# ZIntermediar2024.net
KiCad netlist of a schematic drawn in EAGLE
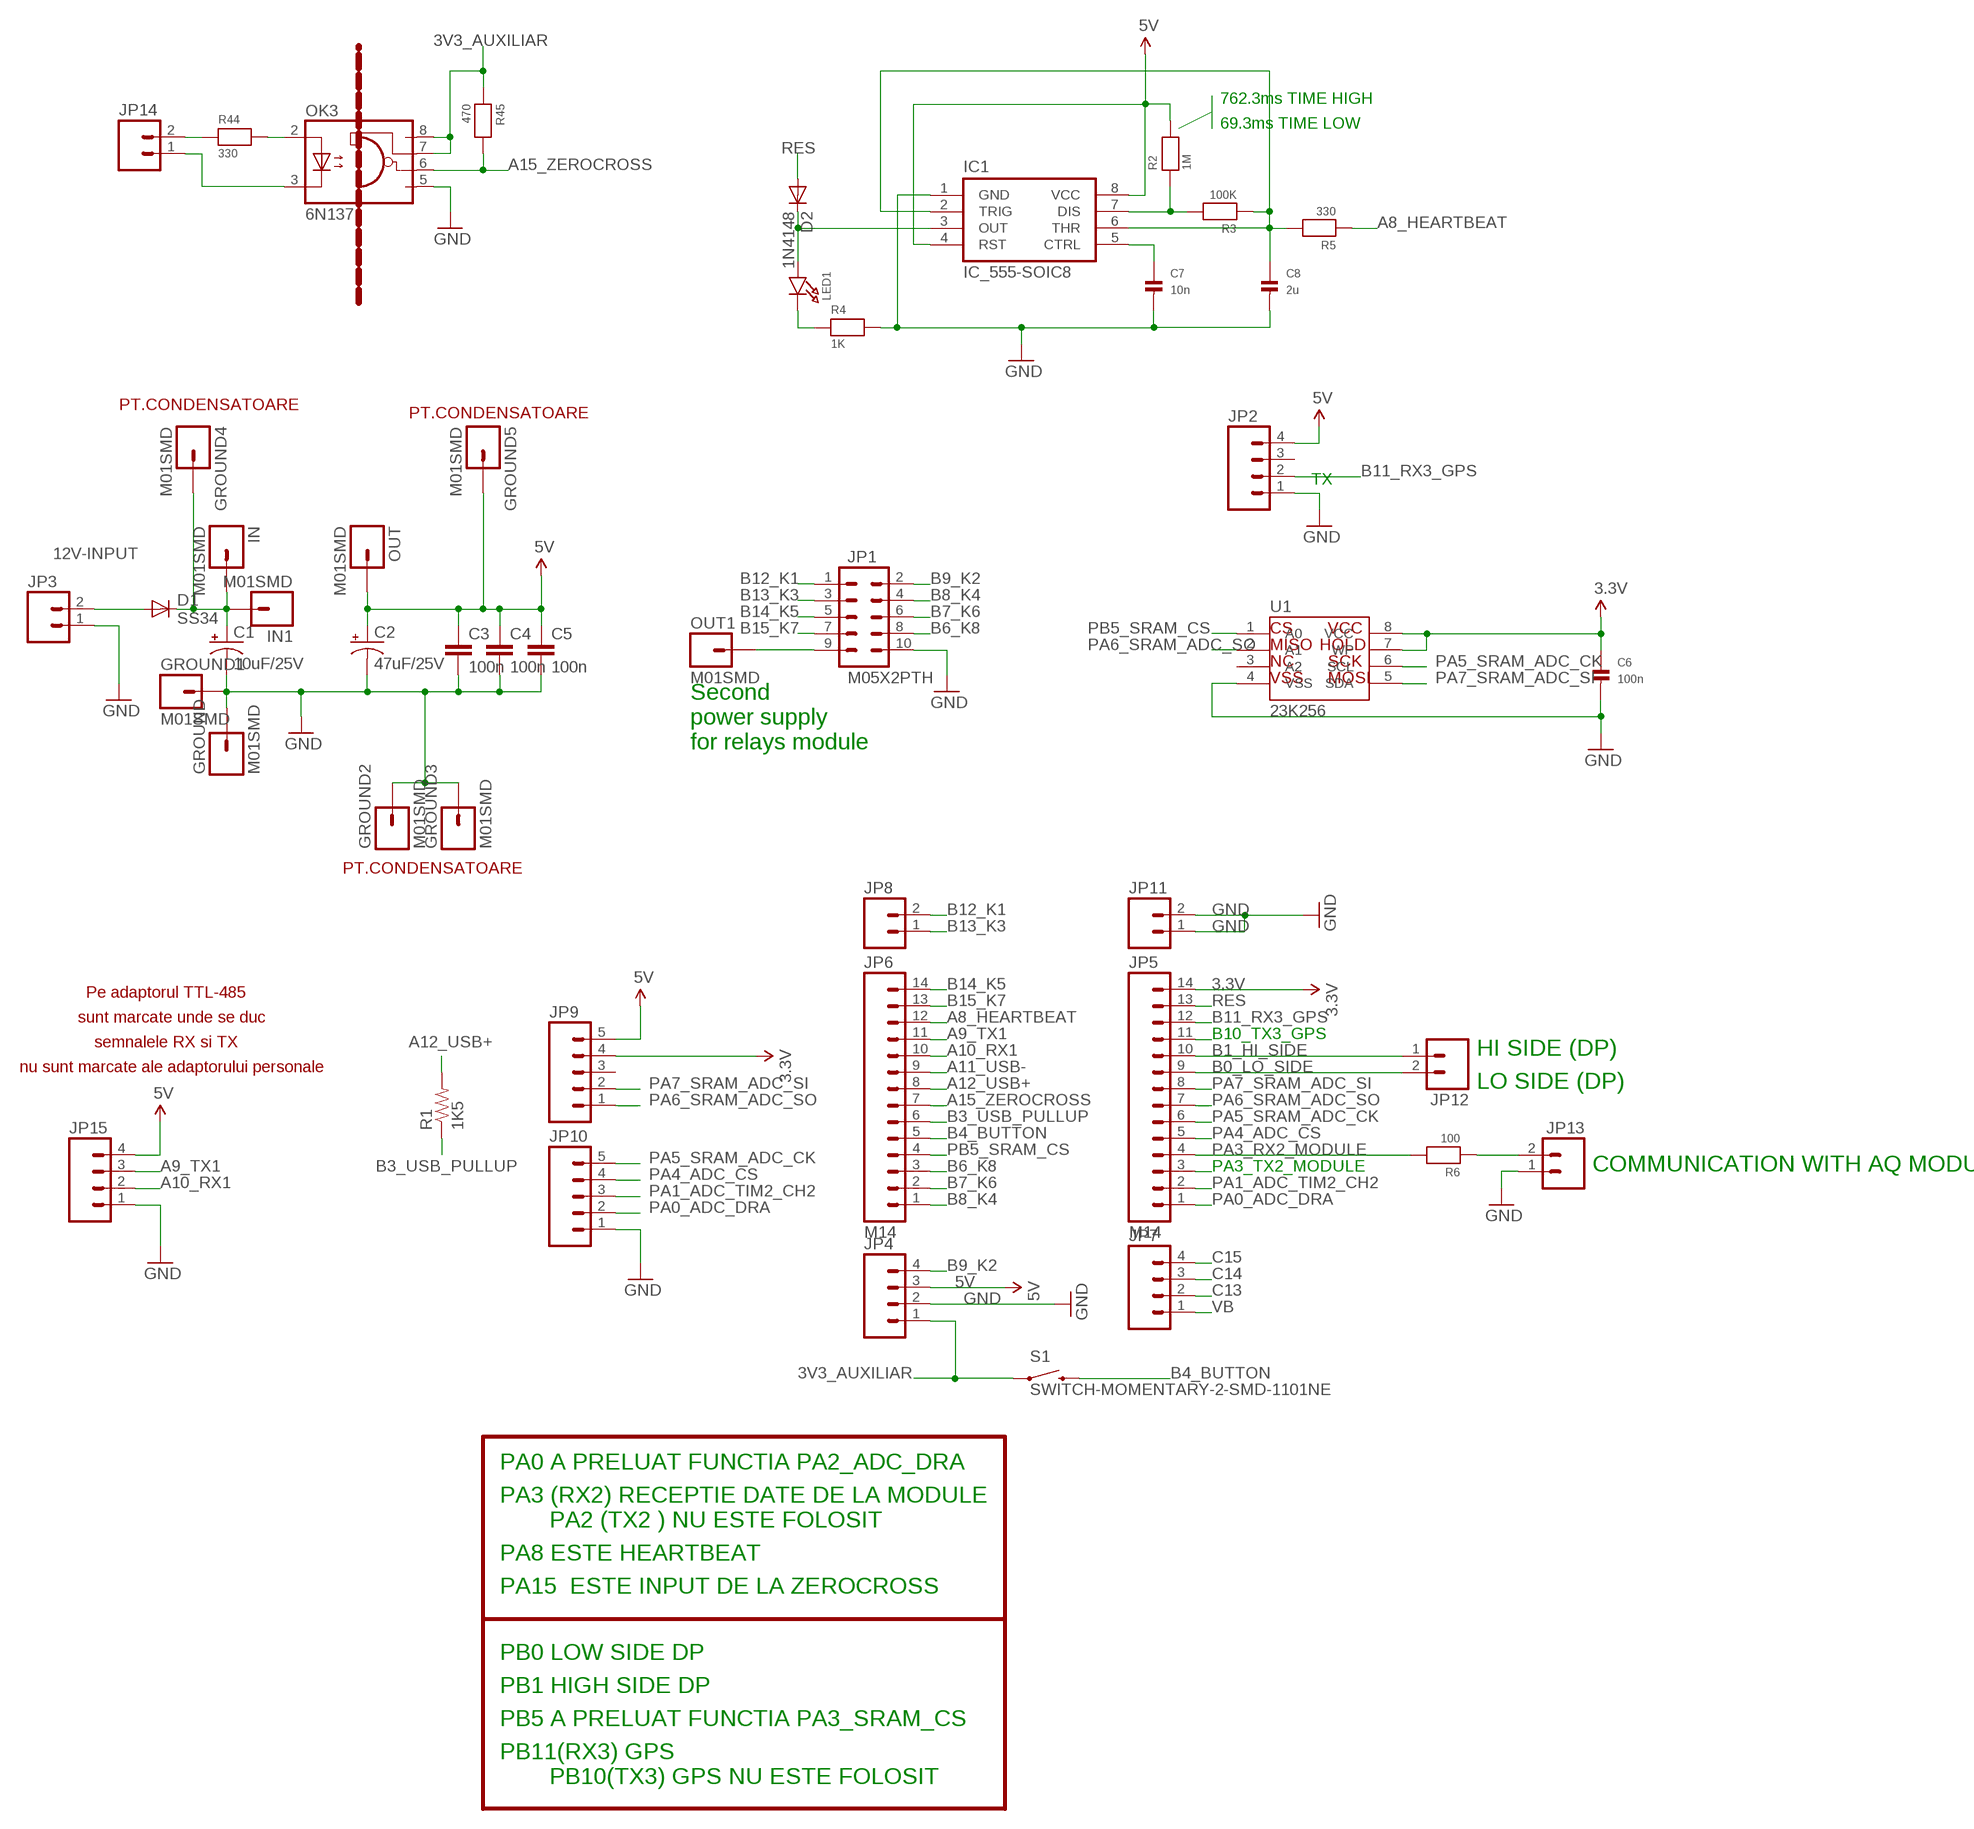
[diagram p0: schematic, sheet 1]

(export (version "E")
  (design (tool "Eeschema 10.0.6"))
  (components
    (comp (ref "C1")
      (value "10uF/25V")
      (footprint "eagle-import:PANASONIC_E")
      (libsource (lib "eagle-import") (part "CAP_POLE"))
    )
    (comp (ref "C2")
      (value "47uF/25V")
      (footprint "eagle-import:PANASONIC_E")
      (libsource (lib "eagle-import") (part "CAP_POLE"))
    )
    (comp (ref "C3")
      (value "100n")
      (footprint "eagle-import:1206")
      (libsource (lib "eagle-import") (part "CAP1206"))
    )
    (comp (ref "C4")
      (value "100n")
      (footprint "eagle-import:1206")
      (libsource (lib "eagle-import") (part "CAP1206"))
    )
    (comp (ref "C5")
      (value "100n")
      (footprint "eagle-import:1206")
      (libsource (lib "eagle-import") (part "CAP1206"))
    )
    (comp (ref "C6")
      (value "100n")
      (footprint "eagle-import:_0805MP")
      (libsource (lib "eagle-import") (part "CAP_CERAMIC_0805MP"))
    )
    (comp (ref "C7")
      (value "10n")
      (footprint "eagle-import:_0805MP")
      (libsource (lib "eagle-import") (part "CAP_CERAMIC_0805MP"))
    )
    (comp (ref "C8")
      (value "2u")
      (footprint "eagle-import:1206")
      (libsource (lib "eagle-import") (part "CAP_CERAMIC1206"))
    )
    (comp (ref "D1")
      (value "SS34")
      (footprint "eagle-import:SMC")
      (libsource (lib "eagle-import") (part "DIODE-SMC"))
    )
    (comp (ref "D2")
      (value "1N4148")
      (footprint "eagle-import:MINIMELF")
      (libsource (lib "eagle-import") (part "DIODE-MINIMELF"))
    )
    (comp (ref "GROUND")
      (value "M01SMD")
      (footprint "eagle-import:LUXEON-PAD")
      (libsource (lib "eagle-import") (part "M01SMD"))
    )
    (comp (ref "GROUND1")
      (value "M01SMD")
      (footprint "eagle-import:LUXEON-PAD")
      (libsource (lib "eagle-import") (part "M01SMD"))
    )
    (comp (ref "GROUND2")
      (value "M01SMD")
      (footprint "eagle-import:LUXEON-PAD")
      (libsource (lib "eagle-import") (part "M01SMD"))
    )
    (comp (ref "GROUND3")
      (value "M01SMD")
      (footprint "eagle-import:LUXEON-PAD")
      (libsource (lib "eagle-import") (part "M01SMD"))
    )
    (comp (ref "GROUND4")
      (value "M01SMD")
      (footprint "eagle-import:LUXEON-PAD")
      (libsource (lib "eagle-import") (part "M01SMD"))
    )
    (comp (ref "GROUND5")
      (value "M01SMD")
      (footprint "eagle-import:LUXEON-PAD")
      (libsource (lib "eagle-import") (part "M01SMD"))
    )
    (comp (ref "IC1")
      (value "IC_555-SOIC8")
      (footprint "eagle-import:SOIC-8")
      (libsource (lib "eagle-import") (part "IC_555-SOIC8"))
    )
    (comp (ref "IN")
      (value "M01SMD")
      (footprint "eagle-import:LUXEON-PAD")
      (libsource (lib "eagle-import") (part "M01SMD"))
    )
    (comp (ref "IN1")
      (value "M01SMD")
      (footprint "eagle-import:LUXEON-PAD")
      (libsource (lib "eagle-import") (part "M01SMD"))
    )
    (comp (ref "JP1")
      (value "M05X2PTH")
      (footprint "eagle-import:AVR_ICSP")
      (libsource (lib "eagle-import") (part "M05X2PTH"))
    )
    (comp (ref "JP2")
      (value "M04PTH")
      (footprint "eagle-import:1X04")
      (libsource (lib "eagle-import") (part "M04PTH"))
    )
    (comp (ref "JP3")
      (value "M025MM")
      (footprint "eagle-import:SCREWTERMINAL-5MM-2")
      (libsource (lib "eagle-import") (part "M025MM"))
    )
    (comp (ref "JP4")
      (value "M04PTH")
      (footprint "eagle-import:1X04")
      (libsource (lib "eagle-import") (part "M04PTH"))
    )
    (comp (ref "JP5")
      (value "M14")
      (footprint "eagle-import:1X14")
      (libsource (lib "eagle-import") (part "M14"))
    )
    (comp (ref "JP6")
      (value "M14")
      (footprint "eagle-import:1X14")
      (libsource (lib "eagle-import") (part "M14"))
    )
    (comp (ref "JP7")
      (value "M04PTH")
      (footprint "eagle-import:1X04")
      (libsource (lib "eagle-import") (part "M04PTH"))
    )
    (comp (ref "JP8")
      (value "M02PTH")
      (footprint "eagle-import:1X02")
      (libsource (lib "eagle-import") (part "M02PTH"))
    )
    (comp (ref "JP9")
      (value "M05PTH_LONGPADS")
      (footprint "eagle-import:1X05_LONGPADS")
      (libsource (lib "eagle-import") (part "M05PTH_LONGPADS"))
    )
    (comp (ref "JP10")
      (value "M05PTH_LONGPADS")
      (footprint "eagle-import:1X05_LONGPADS")
      (libsource (lib "eagle-import") (part "M05PTH_LONGPADS"))
    )
    (comp (ref "JP11")
      (value "M02PTH")
      (footprint "eagle-import:1X02")
      (libsource (lib "eagle-import") (part "M02PTH"))
    )
    (comp (ref "JP12")
      (value "M025MM")
      (footprint "eagle-import:SCREWTERMINAL-5MM-2")
      (libsource (lib "eagle-import") (part "M025MM"))
    )
    (comp (ref "JP13")
      (value "M025MM")
      (footprint "eagle-import:SCREWTERMINAL-5MM-2")
      (libsource (lib "eagle-import") (part "M025MM"))
    )
    (comp (ref "JP14")
      (value "M025MM")
      (footprint "eagle-import:SCREWTERMINAL-5MM-2")
      (libsource (lib "eagle-import") (part "M025MM"))
    )
    (comp (ref "JP15")
      (value "M04LONGPADS")
      (footprint "eagle-import:1X04_LONGPADS")
      (libsource (lib "eagle-import") (part "M04LONGPADS"))
    )
    (comp (ref "LED1")
      (value "LED0805")
      (footprint "eagle-import:CHIPLED_0805")
      (libsource (lib "eagle-import") (part "LED0805"))
    )
    (comp (ref "OK3")
      (value "6N137")
      (footprint "eagle-import:DIL08")
      (libsource (lib "eagle-import") (part "6N137"))
    )
    (comp (ref "OUT")
      (value "M01SMD")
      (footprint "eagle-import:LUXEON-PAD")
      (libsource (lib "eagle-import") (part "M01SMD"))
    )
    (comp (ref "OUT1")
      (value "M01SMD")
      (footprint "eagle-import:LUXEON-PAD")
      (libsource (lib "eagle-import") (part "M01SMD"))
    )
    (comp (ref "R1")
      (value "1K5")
      (footprint "eagle-import:1206")
      (libsource (lib "eagle-import") (part "RESISTOR1206"))
    )
    (comp (ref "R2")
      (value "1M")
      (footprint "eagle-import:_0805MP")
      (libsource (lib "eagle-import") (part "RESISTOR_0805MP"))
    )
    (comp (ref "R3")
      (value "100K")
      (footprint "eagle-import:_0805MP")
      (libsource (lib "eagle-import") (part "RESISTOR_0805MP"))
    )
    (comp (ref "R4")
      (value "1K")
      (footprint "eagle-import:_0805MP")
      (libsource (lib "eagle-import") (part "RESISTOR_0805MP"))
    )
    (comp (ref "R5")
      (value "330")
      (footprint "eagle-import:_0805MP")
      (libsource (lib "eagle-import") (part "RESISTOR_0805MP"))
    )
    (comp (ref "R6")
      (value "100")
      (footprint "eagle-import:_0805MP")
      (libsource (lib "eagle-import") (part "RESISTOR_0805MP"))
    )
    (comp (ref "R44")
      (value "330")
      (footprint "eagle-import:_0805MP")
      (libsource (lib "eagle-import") (part "RESISTOR_0805MP"))
    )
    (comp (ref "R45")
      (value "470")
      (footprint "eagle-import:_0805MP")
      (libsource (lib "eagle-import") (part "RESISTOR_0805MP"))
    )
    (comp (ref "S1")
      (value "SWITCH-MOMENTARY-2-SMD-1101NE")
      (footprint "eagle-import:TACTILE-SWITCH-1101NE")
      (libsource (lib "eagle-import") (part "SWITCH-MOMENTARY-2-SMD-1101NE"))
    )
    (comp (ref "U1")
      (value "23K256")
      (footprint "eagle-import:SO08")
      (libsource (lib "eagle-import") (part "EEPROM-I2CSMD"))
    )
  )
  (nets
    (net (code "1") (name "/3V3_AUXILIAR") (class "Default")
      (node (ref "JP4") (pin "1") (pinfunction "1_1") (pintype "passive"))
      (node (ref "OK3") (pin "7") (pinfunction "VE_7") (pintype "passive"))
      (node (ref "OK3") (pin "8") (pinfunction "VCC_8") (pintype "passive"))
      (node (ref "R45") (pin "1") (pinfunction "1_1") (pintype "passive"))
      (node (ref "S1") (pin "P$1") (pinfunction "1_P$1") (pintype "passive"))
    )
    (net (code "2") (name "/12V-INPUT") (class "Default")
      (node (ref "C1") (pin "+") (pinfunction "+_+") (pintype "passive"))
      (node (ref "D1") (pin "C") (pinfunction "C_C") (pintype "passive"))
      (node (ref "GROUND4") (pin "P$1") (pinfunction "1_P$1") (pintype "passive"))
      (node (ref "IN") (pin "P$1") (pinfunction "1_P$1") (pintype "passive"))
      (node (ref "IN1") (pin "P$1") (pinfunction "1_P$1") (pintype "passive"))
    )
    (net (code "3") (name "/A8_HEARTBEAT") (class "Default")
      (node (ref "JP6") (pin "12") (pinfunction "12_12") (pintype "passive"))
      (node (ref "R5") (pin "1") (pinfunction "1_1") (pintype "passive"))
    )
    (net (code "4") (name "/A9_TX1") (class "Default")
      (node (ref "JP15") (pin "3") (pinfunction "3_3") (pintype "passive"))
      (node (ref "JP6") (pin "11") (pinfunction "11_11") (pintype "passive"))
    )
    (net (code "5") (name "/A10_RX1") (class "Default")
      (node (ref "JP15") (pin "2") (pinfunction "2_2") (pintype "passive"))
      (node (ref "JP6") (pin "10") (pinfunction "10_10") (pintype "passive"))
    )
    (net (code "6") (name "/A11_USB-") (class "Default")
      (node (ref "JP6") (pin "9") (pinfunction "9_9") (pintype "passive"))
    )
    (net (code "7") (name "/A12_USB+") (class "Default")
      (node (ref "JP6") (pin "8") (pinfunction "8_8") (pintype "passive"))
      (node (ref "R1") (pin "2") (pinfunction "2_2") (pintype "passive"))
    )
    (net (code "8") (name "/A15_ZEROCROSS") (class "Default")
      (node (ref "JP6") (pin "7") (pinfunction "7_7") (pintype "passive"))
      (node (ref "OK3") (pin "6") (pinfunction "VO_6") (pintype "passive"))
      (node (ref "R45") (pin "2") (pinfunction "2_2") (pintype "passive"))
    )
    (net (code "9") (name "/B0_LO_SIDE") (class "Default")
      (node (ref "JP12") (pin "2") (pinfunction "2_2") (pintype "passive"))
      (node (ref "JP5") (pin "9") (pinfunction "9_9") (pintype "passive"))
    )
    (net (code "10") (name "/B1_HI_SIDE") (class "Default")
      (node (ref "JP12") (pin "1") (pinfunction "1_1") (pintype "passive"))
      (node (ref "JP5") (pin "10") (pinfunction "10_10") (pintype "passive"))
    )
    (net (code "11") (name "/B3_USB_PULLUP") (class "Default")
      (node (ref "JP6") (pin "6") (pinfunction "6_6") (pintype "passive"))
      (node (ref "R1") (pin "1") (pinfunction "1_1") (pintype "passive"))
    )
    (net (code "12") (name "/B4_BUTTON") (class "Default")
      (node (ref "JP6") (pin "5") (pinfunction "5_5") (pintype "passive"))
      (node (ref "S1") (pin "P$2") (pinfunction "2_P$2") (pintype "passive"))
    )
    (net (code "13") (name "/B6_K8") (class "Default")
      (node (ref "JP1") (pin "8") (pinfunction "8_8") (pintype "passive"))
      (node (ref "JP6") (pin "3") (pinfunction "3_3") (pintype "passive"))
    )
    (net (code "14") (name "/B7_K6") (class "Default")
      (node (ref "JP1") (pin "6") (pinfunction "6_6") (pintype "passive"))
      (node (ref "JP6") (pin "2") (pinfunction "2_2") (pintype "passive"))
    )
    (net (code "15") (name "/B8_K4") (class "Default")
      (node (ref "JP1") (pin "4") (pinfunction "4_4") (pintype "passive"))
      (node (ref "JP6") (pin "1") (pinfunction "1_1") (pintype "passive"))
    )
    (net (code "16") (name "/B9_K2") (class "Default")
      (node (ref "JP1") (pin "2") (pinfunction "2_2") (pintype "passive"))
      (node (ref "JP4") (pin "4") (pinfunction "4_4") (pintype "passive"))
    )
    (net (code "17") (name "/B11_RX3_GPS") (class "Default")
      (node (ref "JP2") (pin "2") (pinfunction "2_2") (pintype "passive"))
      (node (ref "JP5") (pin "12") (pinfunction "12_12") (pintype "passive"))
    )
    (net (code "18") (name "/B12_K1") (class "Default")
      (node (ref "JP1") (pin "1") (pinfunction "1_1") (pintype "passive"))
      (node (ref "JP8") (pin "2") (pinfunction "2_2") (pintype "passive"))
    )
    (net (code "19") (name "/B13_K3") (class "Default")
      (node (ref "JP1") (pin "3") (pinfunction "3_3") (pintype "passive"))
      (node (ref "JP8") (pin "1") (pinfunction "1_1") (pintype "passive"))
    )
    (net (code "20") (name "/B14_K5") (class "Default")
      (node (ref "JP1") (pin "5") (pinfunction "5_5") (pintype "passive"))
      (node (ref "JP6") (pin "14") (pinfunction "14_14") (pintype "passive"))
    )
    (net (code "21") (name "/B15_K7") (class "Default")
      (node (ref "JP1") (pin "7") (pinfunction "7_7") (pintype "passive"))
      (node (ref "JP6") (pin "13") (pinfunction "13_13") (pintype "passive"))
    )
    (net (code "22") (name "/C13") (class "Default")
      (node (ref "JP7") (pin "2") (pinfunction "2_2") (pintype "passive"))
    )
    (net (code "23") (name "/C14") (class "Default")
      (node (ref "JP7") (pin "3") (pinfunction "3_3") (pintype "passive"))
    )
    (net (code "24") (name "/C15") (class "Default")
      (node (ref "JP7") (pin "4") (pinfunction "4_4") (pintype "passive"))
    )
    (net (code "25") (name "/PA0_ADC_DRA") (class "Default")
      (node (ref "JP10") (pin "2") (pinfunction "2_2") (pintype "passive"))
      (node (ref "JP5") (pin "1") (pinfunction "1_1") (pintype "passive"))
    )
    (net (code "26") (name "/PA1_ADC_TIM2_CH2") (class "Default")
      (node (ref "JP10") (pin "3") (pinfunction "3_3") (pintype "passive"))
      (node (ref "JP5") (pin "2") (pinfunction "2_2") (pintype "passive"))
    )
    (net (code "27") (name "/PA3_RX2_MODULE") (class "Default")
      (node (ref "JP5") (pin "4") (pinfunction "4_4") (pintype "passive"))
      (node (ref "R6") (pin "2") (pinfunction "2_2") (pintype "passive"))
    )
    (net (code "28") (name "/PA4_ADC_CS") (class "Default")
      (node (ref "JP10") (pin "4") (pinfunction "4_4") (pintype "passive"))
      (node (ref "JP5") (pin "5") (pinfunction "5_5") (pintype "passive"))
    )
    (net (code "29") (name "/PA5_SRAM_ADC_CK") (class "Default")
      (node (ref "JP10") (pin "5") (pinfunction "5_5") (pintype "passive"))
      (node (ref "JP5") (pin "6") (pinfunction "6_6") (pintype "passive"))
      (node (ref "U1") (pin "6") (pinfunction "SCL_6") (pintype "bidirectional"))
    )
    (net (code "30") (name "/PA6_SRAM_ADC_SO") (class "Default")
      (node (ref "JP5") (pin "7") (pinfunction "7_7") (pintype "passive"))
      (node (ref "JP9") (pin "1") (pinfunction "1_1") (pintype "passive"))
      (node (ref "U1") (pin "2") (pinfunction "A1_2") (pintype "bidirectional"))
    )
    (net (code "31") (name "/PA7_SRAM_ADC_SI") (class "Default")
      (node (ref "JP5") (pin "8") (pinfunction "8_8") (pintype "passive"))
      (node (ref "JP9") (pin "2") (pinfunction "2_2") (pintype "passive"))
      (node (ref "U1") (pin "5") (pinfunction "SDA_5") (pintype "bidirectional"))
    )
    (net (code "32") (name "/PB5_SRAM_CS") (class "Default")
      (node (ref "JP6") (pin "4") (pinfunction "4_4") (pintype "passive"))
      (node (ref "U1") (pin "1") (pinfunction "A0_1") (pintype "bidirectional"))
    )
    (net (code "33") (name "/RES") (class "Default")
      (node (ref "D2") (pin "A") (pinfunction "A_A") (pintype "passive"))
      (node (ref "JP5") (pin "13") (pinfunction "13_13") (pintype "passive"))
    )
    (net (code "34") (name "/VB") (class "Default")
      (node (ref "JP7") (pin "1") (pinfunction "1_1") (pintype "passive"))
    )
    (net (code "35") (name "3.3V") (class "Default")
      (node (ref "C6") (pin "1") (pinfunction "P$1_1") (pintype "passive"))
      (node (ref "JP5") (pin "14") (pinfunction "14_14") (pintype "passive"))
      (node (ref "JP9") (pin "4") (pinfunction "4_4") (pintype "passive"))
      (node (ref "U1") (pin "7") (pinfunction "WP_7") (pintype "bidirectional"))
      (node (ref "U1") (pin "8") (pinfunction "VCC_8") (pintype "power_in"))
    )
    (net (code "36") (name "5V") (class "Default")
      (node (ref "C2") (pin "+") (pinfunction "+_+") (pintype "passive"))
      (node (ref "C3") (pin "1") (pinfunction "1_1") (pintype "passive"))
      (node (ref "C4") (pin "1") (pinfunction "1_1") (pintype "passive"))
      (node (ref "C5") (pin "1") (pinfunction "1_1") (pintype "passive"))
      (node (ref "GROUND5") (pin "P$1") (pinfunction "1_P$1") (pintype "passive"))
      (node (ref "IC1") (pin "4") (pinfunction "RST_4") (pintype "input"))
      (node (ref "IC1") (pin "8") (pinfunction "VCC_8") (pintype "power_in"))
      (node (ref "JP15") (pin "4") (pinfunction "4_4") (pintype "passive"))
      (node (ref "JP2") (pin "4") (pinfunction "4_4") (pintype "passive"))
      (node (ref "JP4") (pin "3") (pinfunction "3_3") (pintype "passive"))
      (node (ref "JP9") (pin "5") (pinfunction "5_5") (pintype "passive"))
      (node (ref "OUT") (pin "P$1") (pinfunction "1_P$1") (pintype "passive"))
      (node (ref "R2") (pin "2") (pinfunction "2_2") (pintype "passive"))
    )
    (net (code "37") (name "GND") (class "Default")
      (node (ref "C1") (pin "-") (pinfunction "-_-") (pintype "passive"))
      (node (ref "C2") (pin "-") (pinfunction "-_-") (pintype "passive"))
      (node (ref "C3") (pin "2") (pinfunction "2_2") (pintype "passive"))
      (node (ref "C4") (pin "2") (pinfunction "2_2") (pintype "passive"))
      (node (ref "C5") (pin "2") (pinfunction "2_2") (pintype "passive"))
      (node (ref "C6") (pin "2") (pinfunction "P$2_2") (pintype "passive"))
      (node (ref "C7") (pin "2") (pinfunction "P$2_2") (pintype "passive"))
      (node (ref "C8") (pin "2") (pinfunction "P$2_2") (pintype "passive"))
      (node (ref "GROUND") (pin "P$1") (pinfunction "1_P$1") (pintype "passive"))
      (node (ref "GROUND1") (pin "P$1") (pinfunction "1_P$1") (pintype "passive"))
      (node (ref "GROUND2") (pin "P$1") (pinfunction "1_P$1") (pintype "passive"))
      (node (ref "GROUND3") (pin "P$1") (pinfunction "1_P$1") (pintype "passive"))
      (node (ref "IC1") (pin "1") (pinfunction "GND_1") (pintype "power_in"))
      (node (ref "JP1") (pin "10") (pinfunction "10_10") (pintype "passive"))
      (node (ref "JP10") (pin "1") (pinfunction "1_1") (pintype "passive"))
      (node (ref "JP11") (pin "1") (pinfunction "1_1") (pintype "passive"))
      (node (ref "JP11") (pin "2") (pinfunction "2_2") (pintype "passive"))
      (node (ref "JP13") (pin "1") (pinfunction "1_1") (pintype "passive"))
      (node (ref "JP15") (pin "1") (pinfunction "1_1") (pintype "passive"))
      (node (ref "JP2") (pin "1") (pinfunction "1_1") (pintype "passive"))
      (node (ref "JP3") (pin "1") (pinfunction "1_1") (pintype "passive"))
      (node (ref "JP4") (pin "2") (pinfunction "2_2") (pintype "passive"))
      (node (ref "OK3") (pin "5") (pinfunction "GND_5") (pintype "passive"))
      (node (ref "R4") (pin "2") (pinfunction "2_2") (pintype "passive"))
      (node (ref "U1") (pin "4") (pinfunction "VSS_4") (pintype "power_in"))
    )
    (net (code "38") (name "Net-(C7-P$1)") (class "Default")
      (node (ref "C7") (pin "1") (pinfunction "P$1_1") (pintype "passive"))
      (node (ref "IC1") (pin "5") (pinfunction "CTRL_5") (pintype "power_in"))
    )
    (net (code "39") (name "Net-(C8-P$1)") (class "Default")
      (node (ref "C8") (pin "1") (pinfunction "P$1_1") (pintype "passive"))
      (node (ref "IC1") (pin "2") (pinfunction "TRIG_2") (pintype "input"))
      (node (ref "IC1") (pin "6") (pinfunction "THR_6") (pintype "input"))
      (node (ref "R3") (pin "1") (pinfunction "1_1") (pintype "passive"))
      (node (ref "R5") (pin "2") (pinfunction "2_2") (pintype "passive"))
    )
    (net (code "40") (name "Net-(D1-PadA)") (class "Default")
      (node (ref "D1") (pin "A") (pinfunction "A_A") (pintype "passive"))
      (node (ref "JP3") (pin "2") (pinfunction "2_2") (pintype "passive"))
    )
    (net (code "41") (name "Net-(IC1-DIS)") (class "Default")
      (node (ref "IC1") (pin "7") (pinfunction "DIS_7") (pintype "input"))
      (node (ref "R2") (pin "1") (pinfunction "1_1") (pintype "passive"))
      (node (ref "R3") (pin "2") (pinfunction "2_2") (pintype "passive"))
    )
    (net (code "42") (name "Net-(IC1-OUT)") (class "Default")
      (node (ref "D2") (pin "C") (pinfunction "C_C") (pintype "passive"))
      (node (ref "IC1") (pin "3") (pinfunction "OUT_3") (pintype "output"))
      (node (ref "LED1") (pin "A") (pinfunction "A_A") (pintype "passive"))
    )
    (net (code "43") (name "Net-(JP13-Pad2)") (class "Default")
      (node (ref "JP13") (pin "2") (pinfunction "2_2") (pintype "passive"))
      (node (ref "R6") (pin "1") (pinfunction "1_1") (pintype "passive"))
    )
    (net (code "44") (name "Net-(JP14-Pad2)") (class "Default")
      (node (ref "JP14") (pin "2") (pinfunction "2_2") (pintype "passive"))
      (node (ref "R44") (pin "1") (pinfunction "1_1") (pintype "passive"))
    )
    (net (code "45") (name "Net-(LED1-PadC)") (class "Default")
      (node (ref "LED1") (pin "C") (pinfunction "C_C") (pintype "passive"))
      (node (ref "R4") (pin "1") (pinfunction "1_1") (pintype "passive"))
    )
    (net (code "46") (name "Net-(OK3-A)") (class "Default")
      (node (ref "OK3") (pin "2") (pinfunction "A_2") (pintype "passive"))
      (node (ref "R44") (pin "2") (pinfunction "2_2") (pintype "passive"))
    )
    (net (code "47") (name "Net-(OK3-C)") (class "Default")
      (node (ref "JP14") (pin "1") (pinfunction "1_1") (pintype "passive"))
      (node (ref "OK3") (pin "3") (pinfunction "C_3") (pintype "passive"))
    )
    (net (code "48") (name "Net-(OUT1-1)") (class "Default")
      (node (ref "JP1") (pin "9") (pinfunction "9_9") (pintype "passive"))
      (node (ref "OUT1") (pin "P$1") (pinfunction "1_P$1") (pintype "passive"))
    )
    (net (code "49") (name "unconnected-(JP2-Pad3)") (class "Default")
      (node (ref "JP2") (pin "3") (pinfunction "3_3") (pintype "passive"))
    )
    (net (code "50") (name "unconnected-(JP5-Pad3)") (class "Default")
      (node (ref "JP5") (pin "3") (pinfunction "3_3") (pintype "passive"))
    )
    (net (code "51") (name "unconnected-(JP5-Pad11)") (class "Default")
      (node (ref "JP5") (pin "11") (pinfunction "11_11") (pintype "passive"))
    )
    (net (code "52") (name "unconnected-(JP9-Pad3)") (class "Default")
      (node (ref "JP9") (pin "3") (pinfunction "3_3") (pintype "passive"))
    )
    (net (code "53") (name "unconnected-(U1-A2-Pad3)") (class "Default")
      (node (ref "U1") (pin "3") (pinfunction "A2_3") (pintype "bidirectional"))
    )
  )
)
